# Pendant.net
KiCad netlist of a schematic drawn in EAGLE
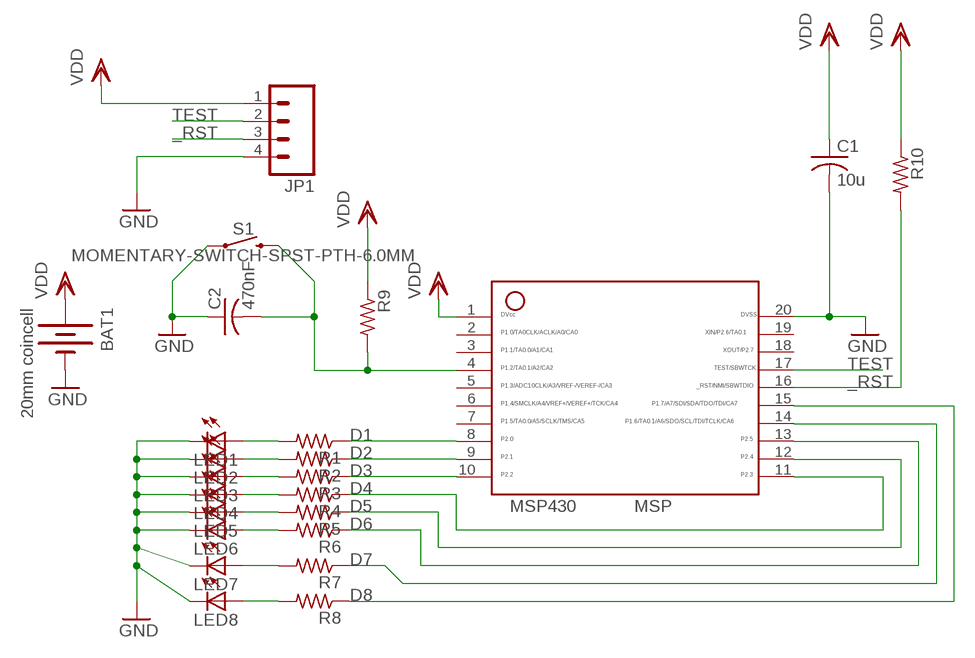
[diagram p0: schematic, sheet 1]

(export (version "E")
  (design (tool "Eeschema 10.0.6"))
  (components
    (comp (ref "BAT1")
      (value "20mm coincell")
      (footprint "eagle-import:BATTCON_20MM_PTH_COMPACT")
      (libsource (lib "eagle-import") (part "BATTERYFOB"))
    )
    (comp (ref "C1")
      (value "10u")
      (footprint "eagle-import:C1206")
      (libsource (lib "eagle-import") (part "C-USC1206"))
    )
    (comp (ref "C2")
      (value "470nF")
      (footprint "eagle-import:C1206")
      (libsource (lib "eagle-import") (part "C-USC1206"))
    )
    (comp (ref "JP1")
      (value "M04LOCK")
      (footprint "eagle-import:1X04_LOCK")
      (libsource (lib "eagle-import") (part "M04LOCK"))
    )
    (comp (ref "LED1")
      (value "LEDCHIPLED_1206")
      (footprint "eagle-import:CHIPLED_1206")
      (libsource (lib "eagle-import") (part "LEDCHIPLED_1206"))
    )
    (comp (ref "LED2")
      (value "LEDCHIPLED_1206")
      (footprint "eagle-import:CHIPLED_1206")
      (libsource (lib "eagle-import") (part "LEDCHIPLED_1206"))
    )
    (comp (ref "LED3")
      (value "LEDCHIPLED_1206")
      (footprint "eagle-import:CHIPLED_1206")
      (libsource (lib "eagle-import") (part "LEDCHIPLED_1206"))
    )
    (comp (ref "LED4")
      (value "LEDCHIPLED_1206")
      (footprint "eagle-import:CHIPLED_1206")
      (libsource (lib "eagle-import") (part "LEDCHIPLED_1206"))
    )
    (comp (ref "LED5")
      (value "LEDCHIPLED_1206")
      (footprint "eagle-import:CHIPLED_1206")
      (libsource (lib "eagle-import") (part "LEDCHIPLED_1206"))
    )
    (comp (ref "LED6")
      (value "LEDCHIPLED_1206")
      (footprint "eagle-import:CHIPLED_1206")
      (libsource (lib "eagle-import") (part "LEDCHIPLED_1206"))
    )
    (comp (ref "LED7")
      (value "LEDCHIPLED_1206")
      (footprint "eagle-import:CHIPLED_1206")
      (libsource (lib "eagle-import") (part "LEDCHIPLED_1206"))
    )
    (comp (ref "LED8")
      (value "LEDCHIPLED_1206")
      (footprint "eagle-import:CHIPLED_1206")
      (libsource (lib "eagle-import") (part "LEDCHIPLED_1206"))
    )
    (comp (ref "MSP430")
      (value "MSP")
      (footprint "eagle-import:20_PIN")
      (libsource (lib "eagle-import") (part "MSP430"))
    )
    (comp (ref "R1")
      (value "R-US_R1206")
      (footprint "eagle-import:R1206")
      (libsource (lib "eagle-import") (part "R-US_R1206"))
    )
    (comp (ref "R2")
      (value "R-US_R1206")
      (footprint "eagle-import:R1206")
      (libsource (lib "eagle-import") (part "R-US_R1206"))
    )
    (comp (ref "R3")
      (value "R-US_R1206")
      (footprint "eagle-import:R1206")
      (libsource (lib "eagle-import") (part "R-US_R1206"))
    )
    (comp (ref "R4")
      (value "R-US_R1206")
      (footprint "eagle-import:R1206")
      (libsource (lib "eagle-import") (part "R-US_R1206"))
    )
    (comp (ref "R5")
      (value "R-US_R1206")
      (footprint "eagle-import:R1206")
      (libsource (lib "eagle-import") (part "R-US_R1206"))
    )
    (comp (ref "R6")
      (value "R-US_R1206")
      (footprint "eagle-import:R1206")
      (libsource (lib "eagle-import") (part "R-US_R1206"))
    )
    (comp (ref "R7")
      (value "R-US_R1206")
      (footprint "eagle-import:R1206")
      (libsource (lib "eagle-import") (part "R-US_R1206"))
    )
    (comp (ref "R8")
      (value "R-US_R1206")
      (footprint "eagle-import:R1206")
      (libsource (lib "eagle-import") (part "R-US_R1206"))
    )
    (comp (ref "R9")
      (value "R-US_R1206")
      (footprint "eagle-import:R1206")
      (libsource (lib "eagle-import") (part "R-US_R1206"))
    )
    (comp (ref "R10")
      (value "R-US_R1206")
      (footprint "eagle-import:R1206")
      (libsource (lib "eagle-import") (part "R-US_R1206"))
    )
    (comp (ref "S1")
      (value "MOMENTARY-SWITCH-SPST-PTH-6.0MM")
      (footprint "eagle-import:TACTILE_SWITCH_PTH_6.0MM")
      (libsource (lib "eagle-import") (part "MOMENTARY-SWITCH-SPST-PTH-6.0MM"))
    )
  )
  (nets
    (net (code "1") (name "/D1") (class "Default")
      (node (ref "MSP430") (pin "8") (pinfunction "8_8") (pintype "bidirectional"))
      (node (ref "R1") (pin "1") (pinfunction "1_1") (pintype "passive"))
    )
    (net (code "2") (name "/D2") (class "Default")
      (node (ref "MSP430") (pin "9") (pinfunction "9_9") (pintype "bidirectional"))
      (node (ref "R2") (pin "1") (pinfunction "1_1") (pintype "passive"))
    )
    (net (code "3") (name "/D3") (class "Default")
      (node (ref "MSP430") (pin "10") (pinfunction "10_10") (pintype "bidirectional"))
      (node (ref "R3") (pin "1") (pinfunction "1_1") (pintype "passive"))
    )
    (net (code "4") (name "/D4") (class "Default")
      (node (ref "MSP430") (pin "11") (pinfunction "11_11") (pintype "bidirectional"))
      (node (ref "R4") (pin "1") (pinfunction "1_1") (pintype "passive"))
    )
    (net (code "5") (name "/D5") (class "Default")
      (node (ref "MSP430") (pin "12") (pinfunction "12_12") (pintype "bidirectional"))
      (node (ref "R5") (pin "1") (pinfunction "1_1") (pintype "passive"))
    )
    (net (code "6") (name "/D6") (class "Default")
      (node (ref "MSP430") (pin "13") (pinfunction "13_13") (pintype "bidirectional"))
      (node (ref "R6") (pin "1") (pinfunction "1_1") (pintype "passive"))
    )
    (net (code "7") (name "/D7") (class "Default")
      (node (ref "MSP430") (pin "14") (pinfunction "14_14") (pintype "bidirectional"))
      (node (ref "R7") (pin "1") (pinfunction "1_1") (pintype "passive"))
    )
    (net (code "8") (name "/D8") (class "Default")
      (node (ref "MSP430") (pin "15") (pinfunction "15_15") (pintype "bidirectional"))
      (node (ref "R8") (pin "1") (pinfunction "1_1") (pintype "passive"))
    )
    (net (code "9") (name "/TEST") (class "Default")
      (node (ref "JP1") (pin "2") (pinfunction "2_2") (pintype "passive"))
      (node (ref "MSP430") (pin "17") (pinfunction "17_17") (pintype "bidirectional"))
    )
    (net (code "10") (name "/_RST") (class "Default")
      (node (ref "JP1") (pin "3") (pinfunction "3_3") (pintype "passive"))
      (node (ref "MSP430") (pin "16") (pinfunction "16_16") (pintype "bidirectional"))
      (node (ref "R10") (pin "2") (pinfunction "2_2") (pintype "passive"))
    )
    (net (code "11") (name "GND") (class "Default")
      (node (ref "BAT1") (pin "2") (pinfunction "-_2") (pintype "power_in"))
      (node (ref "C1") (pin "2") (pinfunction "2_2") (pintype "passive"))
      (node (ref "C2") (pin "1") (pinfunction "1_1") (pintype "passive"))
      (node (ref "JP1") (pin "4") (pinfunction "4_4") (pintype "passive"))
      (node (ref "LED1") (pin "C") (pinfunction "C_C") (pintype "passive"))
      (node (ref "LED2") (pin "C") (pinfunction "C_C") (pintype "passive"))
      (node (ref "LED3") (pin "C") (pinfunction "C_C") (pintype "passive"))
      (node (ref "LED4") (pin "C") (pinfunction "C_C") (pintype "passive"))
      (node (ref "LED5") (pin "C") (pinfunction "C_C") (pintype "passive"))
      (node (ref "LED6") (pin "C") (pinfunction "C_C") (pintype "passive"))
      (node (ref "LED7") (pin "C") (pinfunction "C_C") (pintype "passive"))
      (node (ref "LED8") (pin "C") (pinfunction "C_C") (pintype "passive"))
      (node (ref "MSP430") (pin "20") (pinfunction "20_20") (pintype "bidirectional"))
      (node (ref "S1") (pin "1") (pinfunction "1_1") (pintype "passive"))
    )
    (net (code "12") (name "Net-(LED1-PadA)") (class "Default")
      (node (ref "LED1") (pin "A") (pinfunction "A_A") (pintype "passive"))
      (node (ref "R1") (pin "2") (pinfunction "2_2") (pintype "passive"))
    )
    (net (code "13") (name "Net-(LED2-PadA)") (class "Default")
      (node (ref "LED2") (pin "A") (pinfunction "A_A") (pintype "passive"))
      (node (ref "R2") (pin "2") (pinfunction "2_2") (pintype "passive"))
    )
    (net (code "14") (name "Net-(LED3-PadA)") (class "Default")
      (node (ref "LED3") (pin "A") (pinfunction "A_A") (pintype "passive"))
      (node (ref "R3") (pin "2") (pinfunction "2_2") (pintype "passive"))
    )
    (net (code "15") (name "Net-(LED4-PadA)") (class "Default")
      (node (ref "LED4") (pin "A") (pinfunction "A_A") (pintype "passive"))
      (node (ref "R4") (pin "2") (pinfunction "2_2") (pintype "passive"))
    )
    (net (code "16") (name "Net-(LED5-PadA)") (class "Default")
      (node (ref "LED5") (pin "A") (pinfunction "A_A") (pintype "passive"))
      (node (ref "R5") (pin "2") (pinfunction "2_2") (pintype "passive"))
    )
    (net (code "17") (name "Net-(LED6-PadA)") (class "Default")
      (node (ref "LED6") (pin "A") (pinfunction "A_A") (pintype "passive"))
      (node (ref "R6") (pin "2") (pinfunction "2_2") (pintype "passive"))
    )
    (net (code "18") (name "Net-(LED7-PadA)") (class "Default")
      (node (ref "LED7") (pin "A") (pinfunction "A_A") (pintype "passive"))
      (node (ref "R7") (pin "2") (pinfunction "2_2") (pintype "passive"))
    )
    (net (code "19") (name "Net-(LED8-PadA)") (class "Default")
      (node (ref "LED8") (pin "A") (pinfunction "A_A") (pintype "passive"))
      (node (ref "R8") (pin "2") (pinfunction "2_2") (pintype "passive"))
    )
    (net (code "20") (name "Net-(S1-2)") (class "Default")
      (node (ref "C2") (pin "2") (pinfunction "2_2") (pintype "passive"))
      (node (ref "MSP430") (pin "4") (pinfunction "4_4") (pintype "bidirectional"))
      (node (ref "R9") (pin "2") (pinfunction "2_2") (pintype "passive"))
      (node (ref "S1") (pin "3") (pinfunction "2_3") (pintype "passive"))
    )
    (net (code "21") (name "VDD") (class "Default")
      (node (ref "BAT1") (pin "1") (pinfunction "+_1") (pintype "power_in"))
      (node (ref "BAT1") (pin "3") (pinfunction "+_3") (pintype "power_in"))
      (node (ref "BAT1") (pin "4") (pinfunction "+_4") (pintype "power_in"))
      (node (ref "BAT1") (pin "5") (pinfunction "+_5") (pintype "power_in"))
      (node (ref "C1") (pin "1") (pinfunction "1_1") (pintype "passive"))
      (node (ref "JP1") (pin "1") (pinfunction "1_1") (pintype "passive"))
      (node (ref "MSP430") (pin "1") (pinfunction "1_1") (pintype "bidirectional"))
      (node (ref "R10") (pin "1") (pinfunction "1_1") (pintype "passive"))
      (node (ref "R9") (pin "1") (pinfunction "1_1") (pintype "passive"))
    )
    (net (code "22") (name "unconnected-(MSP430-Pad2)") (class "Default")
      (node (ref "MSP430") (pin "2") (pinfunction "2_2") (pintype "bidirectional"))
    )
    (net (code "23") (name "unconnected-(MSP430-Pad3)") (class "Default")
      (node (ref "MSP430") (pin "3") (pinfunction "3_3") (pintype "bidirectional"))
    )
    (net (code "24") (name "unconnected-(MSP430-Pad5)") (class "Default")
      (node (ref "MSP430") (pin "5") (pinfunction "5_5") (pintype "bidirectional"))
    )
    (net (code "25") (name "unconnected-(MSP430-Pad6)") (class "Default")
      (node (ref "MSP430") (pin "6") (pinfunction "6_6") (pintype "bidirectional"))
    )
    (net (code "26") (name "unconnected-(MSP430-Pad7)") (class "Default")
      (node (ref "MSP430") (pin "7") (pinfunction "7_7") (pintype "bidirectional"))
    )
    (net (code "27") (name "unconnected-(MSP430-Pad18)") (class "Default")
      (node (ref "MSP430") (pin "18") (pinfunction "18_18") (pintype "bidirectional"))
    )
    (net (code "28") (name "unconnected-(MSP430-Pad19)") (class "Default")
      (node (ref "MSP430") (pin "19") (pinfunction "19_19") (pintype "bidirectional"))
    )
  )
)
